# Dosing_CTRLR_HMI.net
KiCad netlist of a schematic drawn in EAGLE
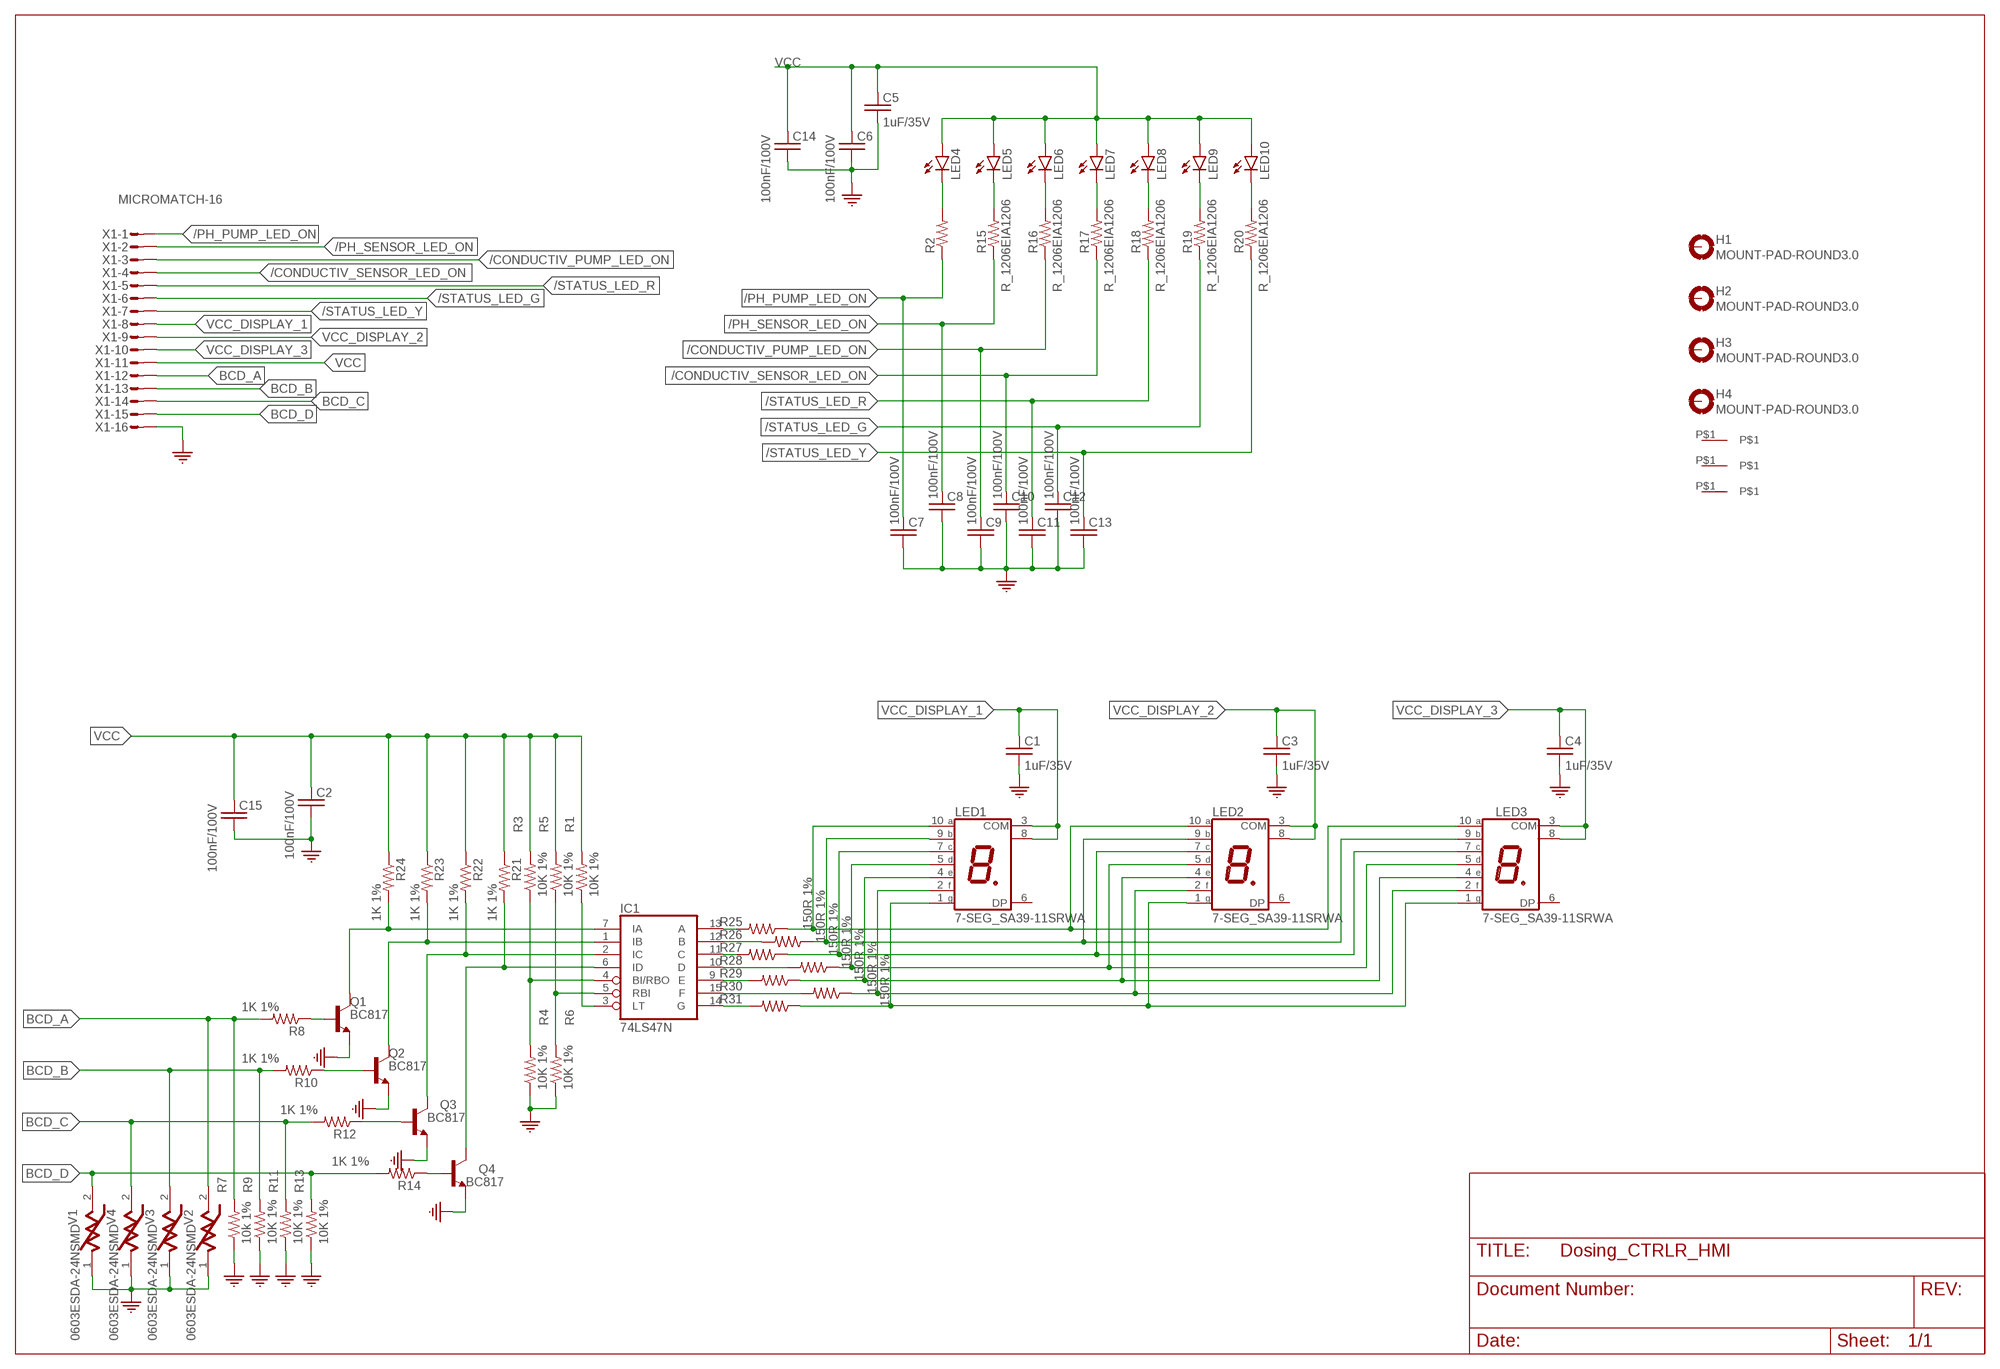
[diagram p0: schematic, sheet 1]

(export (version "E")
  (design (tool "Eeschema 10.0.6"))
  (components
    (comp (ref "C1")
      (value "1uF/35V")
      (footprint "eagle-import:EIA0603")
      (libsource (lib "eagle-import") (part "C_0603EIA0603"))
    )
    (comp (ref "C2")
      (value "100nF/100V")
      (footprint "eagle-import:EIA0603")
      (libsource (lib "eagle-import") (part "C_0603EIA0603"))
    )
    (comp (ref "C3")
      (value "1uF/35V")
      (footprint "eagle-import:EIA0603")
      (libsource (lib "eagle-import") (part "C_0603EIA0603"))
    )
    (comp (ref "C4")
      (value "1uF/35V")
      (footprint "eagle-import:EIA0603")
      (libsource (lib "eagle-import") (part "C_0603EIA0603"))
    )
    (comp (ref "C5")
      (value "1uF/35V")
      (footprint "eagle-import:EIA0603")
      (libsource (lib "eagle-import") (part "C_0603EIA0603"))
    )
    (comp (ref "C6")
      (value "100nF/100V")
      (footprint "eagle-import:EIA0603")
      (libsource (lib "eagle-import") (part "C_0603EIA0603"))
    )
    (comp (ref "C7")
      (value "100nF/100V")
      (footprint "eagle-import:EIA0603")
      (libsource (lib "eagle-import") (part "C_0603EIA0603"))
    )
    (comp (ref "C8")
      (value "100nF/100V")
      (footprint "eagle-import:EIA0603")
      (libsource (lib "eagle-import") (part "C_0603EIA0603"))
    )
    (comp (ref "C9")
      (value "100nF/100V")
      (footprint "eagle-import:EIA0603")
      (libsource (lib "eagle-import") (part "C_0603EIA0603"))
    )
    (comp (ref "C10")
      (value "100nF/100V")
      (footprint "eagle-import:EIA0603")
      (libsource (lib "eagle-import") (part "C_0603EIA0603"))
    )
    (comp (ref "C11")
      (value "100nF/100V")
      (footprint "eagle-import:EIA0603")
      (libsource (lib "eagle-import") (part "C_0603EIA0603"))
    )
    (comp (ref "C12")
      (value "100nF/100V")
      (footprint "eagle-import:EIA0603")
      (libsource (lib "eagle-import") (part "C_0603EIA0603"))
    )
    (comp (ref "C13")
      (value "100nF/100V")
      (footprint "eagle-import:EIA0603")
      (libsource (lib "eagle-import") (part "C_0603EIA0603"))
    )
    (comp (ref "C14")
      (value "100nF/100V")
      (footprint "eagle-import:EIA0603")
      (libsource (lib "eagle-import") (part "C_0603EIA0603"))
    )
    (comp (ref "C15")
      (value "100nF/100V")
      (footprint "eagle-import:EIA0603")
      (libsource (lib "eagle-import") (part "C_0603EIA0603"))
    )
    (comp (ref "FID1")
      (value "FIDUCIAL")
      (footprint "eagle-import:FIDUCIAL")
      (libsource (lib "eagle-import") (part "FIDUCIAL"))
    )
    (comp (ref "FID2")
      (value "FIDUCIAL")
      (footprint "eagle-import:FIDUCIAL")
      (libsource (lib "eagle-import") (part "FIDUCIAL"))
    )
    (comp (ref "FID3")
      (value "FIDUCIAL")
      (footprint "eagle-import:FIDUCIAL")
      (libsource (lib "eagle-import") (part "FIDUCIAL"))
    )
    (comp (ref "H1")
      (value "MOUNT-PAD-ROUND3.0")
      (footprint "eagle-import:3,0-PAD")
      (libsource (lib "eagle-import") (part "MOUNT-PAD-ROUND3.0"))
    )
    (comp (ref "H2")
      (value "MOUNT-PAD-ROUND3.0")
      (footprint "eagle-import:3,0-PAD")
      (libsource (lib "eagle-import") (part "MOUNT-PAD-ROUND3.0"))
    )
    (comp (ref "H3")
      (value "MOUNT-PAD-ROUND3.0")
      (footprint "eagle-import:3,0-PAD")
      (libsource (lib "eagle-import") (part "MOUNT-PAD-ROUND3.0"))
    )
    (comp (ref "H4")
      (value "MOUNT-PAD-ROUND3.0")
      (footprint "eagle-import:3,0-PAD")
      (libsource (lib "eagle-import") (part "MOUNT-PAD-ROUND3.0"))
    )
    (comp (ref "IC1")
      (value "74LS47N")
      (footprint "eagle-import:DIL16")
      (libsource (lib "eagle-import") (part "7447NLS"))
    )
    (comp (ref "LED1")
      (value "7-SEG_SA39-11SRWA")
      (footprint "eagle-import:SA39-11SRWA")
      (libsource (lib "eagle-import") (part "7-SEG_SA39-11SRWA"))
    )
    (comp (ref "LED2")
      (value "7-SEG_SA39-11SRWA")
      (footprint "eagle-import:SA39-11SRWA")
      (libsource (lib "eagle-import") (part "7-SEG_SA39-11SRWA"))
    )
    (comp (ref "LED3")
      (value "7-SEG_SA39-11SRWA")
      (footprint "eagle-import:SA39-11SRWA")
      (libsource (lib "eagle-import") (part "7-SEG_SA39-11SRWA"))
    )
    (comp (ref "LED4")
      (value "LED5MM")
      (footprint "eagle-import:LED5MM")
      (libsource (lib "eagle-import") (part "LED5MM"))
    )
    (comp (ref "LED5")
      (value "LED5MM")
      (footprint "eagle-import:LED5MM")
      (libsource (lib "eagle-import") (part "LED5MM"))
    )
    (comp (ref "LED6")
      (value "LED5MM")
      (footprint "eagle-import:LED5MM")
      (libsource (lib "eagle-import") (part "LED5MM"))
    )
    (comp (ref "LED7")
      (value "LED5MM")
      (footprint "eagle-import:LED5MM")
      (libsource (lib "eagle-import") (part "LED5MM"))
    )
    (comp (ref "LED8")
      (value "LED5MM")
      (footprint "eagle-import:LED5MM")
      (libsource (lib "eagle-import") (part "LED5MM"))
    )
    (comp (ref "LED9")
      (value "LED5MM")
      (footprint "eagle-import:LED5MM")
      (libsource (lib "eagle-import") (part "LED5MM"))
    )
    (comp (ref "LED10")
      (value "LED5MM")
      (footprint "eagle-import:LED5MM")
      (libsource (lib "eagle-import") (part "LED5MM"))
    )
    (comp (ref "Q1")
      (value "BC817")
      (footprint "eagle-import:SOT23")
      (fields (field (name "MFR") "NXP"))
      (libsource (lib "eagle-import") (part "BC817"))
    )
    (comp (ref "Q2")
      (value "BC817")
      (footprint "eagle-import:SOT23")
      (fields (field (name "MFR") "NXP"))
      (libsource (lib "eagle-import") (part "BC817"))
    )
    (comp (ref "Q3")
      (value "BC817")
      (footprint "eagle-import:SOT23")
      (fields (field (name "MFR") "NXP"))
      (libsource (lib "eagle-import") (part "BC817"))
    )
    (comp (ref "Q4")
      (value "BC817")
      (footprint "eagle-import:SOT23")
      (fields (field (name "MFR") "NXP"))
      (libsource (lib "eagle-import") (part "BC817"))
    )
    (comp (ref "R1")
      (value "10K 1%")
      (footprint "eagle-import:EIA0603")
      (libsource (lib "eagle-import") (part "R_0603"))
    )
    (comp (ref "R2")
      (value "R_1206EIA1206")
      (footprint "eagle-import:EIA1206")
      (libsource (lib "eagle-import") (part "R_1206EIA1206"))
    )
    (comp (ref "R3")
      (value "10K 1%")
      (footprint "eagle-import:EIA0603")
      (libsource (lib "eagle-import") (part "R_0603"))
    )
    (comp (ref "R4")
      (value "10K 1%")
      (footprint "eagle-import:EIA0603")
      (libsource (lib "eagle-import") (part "R_0603"))
    )
    (comp (ref "R5")
      (value "10K 1%")
      (footprint "eagle-import:EIA0603")
      (libsource (lib "eagle-import") (part "R_0603"))
    )
    (comp (ref "R6")
      (value "10K 1%")
      (footprint "eagle-import:EIA0603")
      (libsource (lib "eagle-import") (part "R_0603"))
    )
    (comp (ref "R7")
      (value "10k 1%")
      (footprint "eagle-import:EIA0603")
      (libsource (lib "eagle-import") (part "R_0603"))
    )
    (comp (ref "R8")
      (value "1K 1%")
      (footprint "eagle-import:EIA0603")
      (libsource (lib "eagle-import") (part "R_0603"))
    )
    (comp (ref "R9")
      (value "10K 1%")
      (footprint "eagle-import:EIA0603")
      (libsource (lib "eagle-import") (part "R_0603"))
    )
    (comp (ref "R10")
      (value "1K 1%")
      (footprint "eagle-import:EIA0603")
      (libsource (lib "eagle-import") (part "R_0603"))
    )
    (comp (ref "R11")
      (value "10K 1%")
      (footprint "eagle-import:EIA0603")
      (libsource (lib "eagle-import") (part "R_0603"))
    )
    (comp (ref "R12")
      (value "1K 1%")
      (footprint "eagle-import:EIA0603")
      (libsource (lib "eagle-import") (part "R_0603"))
    )
    (comp (ref "R13")
      (value "10K 1%")
      (footprint "eagle-import:EIA0603")
      (libsource (lib "eagle-import") (part "R_0603"))
    )
    (comp (ref "R14")
      (value "1K 1%")
      (footprint "eagle-import:EIA0603")
      (libsource (lib "eagle-import") (part "R_0603"))
    )
    (comp (ref "R15")
      (value "R_1206EIA1206")
      (footprint "eagle-import:EIA1206")
      (libsource (lib "eagle-import") (part "R_1206EIA1206"))
    )
    (comp (ref "R16")
      (value "R_1206EIA1206")
      (footprint "eagle-import:EIA1206")
      (libsource (lib "eagle-import") (part "R_1206EIA1206"))
    )
    (comp (ref "R17")
      (value "R_1206EIA1206")
      (footprint "eagle-import:EIA1206")
      (libsource (lib "eagle-import") (part "R_1206EIA1206"))
    )
    (comp (ref "R18")
      (value "R_1206EIA1206")
      (footprint "eagle-import:EIA1206")
      (libsource (lib "eagle-import") (part "R_1206EIA1206"))
    )
    (comp (ref "R19")
      (value "R_1206EIA1206")
      (footprint "eagle-import:EIA1206")
      (libsource (lib "eagle-import") (part "R_1206EIA1206"))
    )
    (comp (ref "R20")
      (value "R_1206EIA1206")
      (footprint "eagle-import:EIA1206")
      (libsource (lib "eagle-import") (part "R_1206EIA1206"))
    )
    (comp (ref "R21")
      (value "1K 1%")
      (footprint "eagle-import:EIA0603")
      (libsource (lib "eagle-import") (part "R_0603"))
    )
    (comp (ref "R22")
      (value "1K 1%")
      (footprint "eagle-import:EIA0603")
      (libsource (lib "eagle-import") (part "R_0603"))
    )
    (comp (ref "R23")
      (value "1K 1%")
      (footprint "eagle-import:EIA0603")
      (libsource (lib "eagle-import") (part "R_0603"))
    )
    (comp (ref "R24")
      (value "1K 1%")
      (footprint "eagle-import:EIA0603")
      (libsource (lib "eagle-import") (part "R_0603"))
    )
    (comp (ref "R25")
      (value "150R 1%")
      (footprint "eagle-import:EIA1206")
      (libsource (lib "eagle-import") (part "R_1206EIA1206"))
    )
    (comp (ref "R26")
      (value "150R 1%")
      (footprint "eagle-import:EIA1206")
      (libsource (lib "eagle-import") (part "R_1206EIA1206"))
    )
    (comp (ref "R27")
      (value "150R 1%")
      (footprint "eagle-import:EIA1206")
      (libsource (lib "eagle-import") (part "R_1206EIA1206"))
    )
    (comp (ref "R28")
      (value "150R 1%")
      (footprint "eagle-import:EIA1206")
      (libsource (lib "eagle-import") (part "R_1206EIA1206"))
    )
    (comp (ref "R29")
      (value "150R 1%")
      (footprint "eagle-import:EIA1206")
      (libsource (lib "eagle-import") (part "R_1206EIA1206"))
    )
    (comp (ref "R30")
      (value "150R 1%")
      (footprint "eagle-import:EIA1206")
      (libsource (lib "eagle-import") (part "R_1206EIA1206"))
    )
    (comp (ref "R31")
      (value "150R 1%")
      (footprint "eagle-import:EIA1206")
      (libsource (lib "eagle-import") (part "R_1206EIA1206"))
    )
    (comp (ref "V1")
      (value "0603ESDA-24NSMD")
      (footprint "eagle-import:EIA0603")
      (fields (field (name "MFR") "Bourns"))
      (libsource (lib "eagle-import") (part "0603ESDA-24NSMD"))
    )
    (comp (ref "V2")
      (value "0603ESDA-24NSMD")
      (footprint "eagle-import:EIA0603")
      (fields (field (name "MFR") "Bourns"))
      (libsource (lib "eagle-import") (part "0603ESDA-24NSMD"))
    )
    (comp (ref "V3")
      (value "0603ESDA-24NSMD")
      (footprint "eagle-import:EIA0603")
      (fields (field (name "MFR") "Bourns"))
      (libsource (lib "eagle-import") (part "0603ESDA-24NSMD"))
    )
    (comp (ref "V4")
      (value "0603ESDA-24NSMD")
      (footprint "eagle-import:EIA0603")
      (fields (field (name "MFR") "Bourns"))
      (libsource (lib "eagle-import") (part "0603ESDA-24NSMD"))
    )
    (comp (ref "X1")
      (value "MICROMATCH-16")
      (footprint "eagle-import:MICROMATCH-16")
      (fields (field (name "MF") "FARNELL") (field (name "MPN") "8-215464-6"))
      (libsource (lib "eagle-import") (part "MICROMATCH-16"))
    )
  )
  (nets
    (net (code "1") (name "BCD_A") (class "Default")
      (node (ref "R7") (pin "2") (pinfunction "2_2") (pintype "passive"))
      (node (ref "R8") (pin "2") (pinfunction "2_2") (pintype "passive"))
      (node (ref "V2") (pin "2") (pinfunction "2_2") (pintype "passive"))
      (node (ref "X1") (pin "12") (pinfunction "S_12") (pintype "passive"))
    )
    (net (code "2") (name "BCD_B") (class "Default")
      (node (ref "R10") (pin "2") (pinfunction "2_2") (pintype "passive"))
      (node (ref "R9") (pin "2") (pinfunction "2_2") (pintype "passive"))
      (node (ref "V3") (pin "2") (pinfunction "2_2") (pintype "passive"))
      (node (ref "X1") (pin "13") (pinfunction "S_13") (pintype "passive"))
    )
    (net (code "3") (name "BCD_C") (class "Default")
      (node (ref "R11") (pin "2") (pinfunction "2_2") (pintype "passive"))
      (node (ref "R12") (pin "2") (pinfunction "2_2") (pintype "passive"))
      (node (ref "V4") (pin "2") (pinfunction "2_2") (pintype "passive"))
      (node (ref "X1") (pin "14") (pinfunction "S_14") (pintype "passive"))
    )
    (net (code "4") (name "BCD_D") (class "Default")
      (node (ref "R13") (pin "2") (pinfunction "2_2") (pintype "passive"))
      (node (ref "R14") (pin "2") (pinfunction "2_2") (pintype "passive"))
      (node (ref "V1") (pin "2") (pinfunction "2_2") (pintype "passive"))
      (node (ref "X1") (pin "15") (pinfunction "S_15") (pintype "passive"))
    )
    (net (code "5") (name "GND") (class "Default")
      (node (ref "C1") (pin "2") (pinfunction "2_2") (pintype "passive"))
      (node (ref "C10") (pin "2") (pinfunction "2_2") (pintype "passive"))
      (node (ref "C11") (pin "2") (pinfunction "2_2") (pintype "passive"))
      (node (ref "C12") (pin "2") (pinfunction "2_2") (pintype "passive"))
      (node (ref "C13") (pin "2") (pinfunction "2_2") (pintype "passive"))
      (node (ref "C14") (pin "2") (pinfunction "2_2") (pintype "passive"))
      (node (ref "C15") (pin "2") (pinfunction "2_2") (pintype "passive"))
      (node (ref "C2") (pin "2") (pinfunction "2_2") (pintype "passive"))
      (node (ref "C3") (pin "2") (pinfunction "2_2") (pintype "passive"))
      (node (ref "C4") (pin "2") (pinfunction "2_2") (pintype "passive"))
      (node (ref "C5") (pin "2") (pinfunction "2_2") (pintype "passive"))
      (node (ref "C6") (pin "2") (pinfunction "2_2") (pintype "passive"))
      (node (ref "C7") (pin "2") (pinfunction "2_2") (pintype "passive"))
      (node (ref "C8") (pin "2") (pinfunction "2_2") (pintype "passive"))
      (node (ref "C9") (pin "2") (pinfunction "2_2") (pintype "passive"))
      (node (ref "Q1") (pin "2") (pinfunction "E_2") (pintype "passive"))
      (node (ref "Q2") (pin "2") (pinfunction "E_2") (pintype "passive"))
      (node (ref "Q3") (pin "2") (pinfunction "E_2") (pintype "passive"))
      (node (ref "Q4") (pin "2") (pinfunction "E_2") (pintype "passive"))
      (node (ref "R11") (pin "1") (pinfunction "1_1") (pintype "passive"))
      (node (ref "R13") (pin "1") (pinfunction "1_1") (pintype "passive"))
      (node (ref "R4") (pin "1") (pinfunction "1_1") (pintype "passive"))
      (node (ref "R6") (pin "1") (pinfunction "1_1") (pintype "passive"))
      (node (ref "R7") (pin "1") (pinfunction "1_1") (pintype "passive"))
      (node (ref "R9") (pin "1") (pinfunction "1_1") (pintype "passive"))
      (node (ref "V1") (pin "1") (pinfunction "1_1") (pintype "passive"))
      (node (ref "V2") (pin "1") (pinfunction "1_1") (pintype "passive"))
      (node (ref "V3") (pin "1") (pinfunction "1_1") (pintype "passive"))
      (node (ref "V4") (pin "1") (pinfunction "1_1") (pintype "passive"))
      (node (ref "X1") (pin "16") (pinfunction "S_16") (pintype "passive"))
    )
    (net (code "6") (name "Net-(IC1A-A)") (class "Default")
      (node (ref "IC1") (pin "13") (pinfunction "A_13") (pintype "output"))
      (node (ref "R25") (pin "2") (pinfunction "2_2") (pintype "passive"))
    )
    (net (code "7") (name "Net-(IC1A-B)") (class "Default")
      (node (ref "IC1") (pin "12") (pinfunction "B_12") (pintype "output"))
      (node (ref "R26") (pin "2") (pinfunction "2_2") (pintype "passive"))
    )
    (net (code "8") (name "Net-(IC1A-BI{slash}RBO)") (class "Default")
      (node (ref "IC1") (pin "4") (pinfunction "BI/RBO_4") (pintype "input"))
      (node (ref "R3") (pin "1") (pinfunction "1_1") (pintype "passive"))
      (node (ref "R4") (pin "2") (pinfunction "2_2") (pintype "passive"))
    )
    (net (code "9") (name "Net-(IC1A-C)") (class "Default")
      (node (ref "IC1") (pin "11") (pinfunction "C_11") (pintype "output"))
      (node (ref "R27") (pin "2") (pinfunction "2_2") (pintype "passive"))
    )
    (net (code "10") (name "Net-(IC1A-D)") (class "Default")
      (node (ref "IC1") (pin "10") (pinfunction "D_10") (pintype "output"))
      (node (ref "R28") (pin "2") (pinfunction "2_2") (pintype "passive"))
    )
    (net (code "11") (name "Net-(IC1A-E)") (class "Default")
      (node (ref "IC1") (pin "9") (pinfunction "E_9") (pintype "output"))
      (node (ref "R29") (pin "2") (pinfunction "2_2") (pintype "passive"))
    )
    (net (code "12") (name "Net-(IC1A-F)") (class "Default")
      (node (ref "IC1") (pin "15") (pinfunction "F_15") (pintype "output"))
      (node (ref "R30") (pin "2") (pinfunction "2_2") (pintype "passive"))
    )
    (net (code "13") (name "Net-(IC1A-G)") (class "Default")
      (node (ref "IC1") (pin "14") (pinfunction "G_14") (pintype "output"))
      (node (ref "R31") (pin "2") (pinfunction "2_2") (pintype "passive"))
    )
    (net (code "14") (name "Net-(IC1A-IA)") (class "Default")
      (node (ref "IC1") (pin "7") (pinfunction "IA_7") (pintype "input"))
      (node (ref "Q1") (pin "3") (pinfunction "C_3") (pintype "passive"))
      (node (ref "R24") (pin "2") (pinfunction "2_2") (pintype "passive"))
    )
    (net (code "15") (name "Net-(IC1A-IB)") (class "Default")
      (node (ref "IC1") (pin "1") (pinfunction "IB_1") (pintype "input"))
      (node (ref "Q2") (pin "3") (pinfunction "C_3") (pintype "passive"))
      (node (ref "R23") (pin "2") (pinfunction "2_2") (pintype "passive"))
    )
    (net (code "16") (name "Net-(IC1A-IC)") (class "Default")
      (node (ref "IC1") (pin "2") (pinfunction "IC_2") (pintype "input"))
      (node (ref "Q3") (pin "3") (pinfunction "C_3") (pintype "passive"))
      (node (ref "R22") (pin "2") (pinfunction "2_2") (pintype "passive"))
    )
    (net (code "17") (name "Net-(IC1A-ID)") (class "Default")
      (node (ref "IC1") (pin "6") (pinfunction "ID_6") (pintype "input"))
      (node (ref "Q4") (pin "3") (pinfunction "C_3") (pintype "passive"))
      (node (ref "R21") (pin "2") (pinfunction "2_2") (pintype "passive"))
    )
    (net (code "18") (name "Net-(IC1A-LT)") (class "Default")
      (node (ref "IC1") (pin "3") (pinfunction "LT_3") (pintype "input"))
      (node (ref "R1") (pin "1") (pinfunction "1_1") (pintype "passive"))
    )
    (net (code "19") (name "Net-(IC1A-RBI)") (class "Default")
      (node (ref "IC1") (pin "5") (pinfunction "RBI_5") (pintype "input"))
      (node (ref "R5") (pin "1") (pinfunction "1_1") (pintype "passive"))
      (node (ref "R6") (pin "2") (pinfunction "2_2") (pintype "passive"))
    )
    (net (code "20") (name "Net-(LED1-A)") (class "Default")
      (node (ref "LED1") (pin "10") (pinfunction "A_10") (pintype "passive"))
      (node (ref "LED2") (pin "10") (pinfunction "A_10") (pintype "passive"))
      (node (ref "LED3") (pin "10") (pinfunction "A_10") (pintype "passive"))
      (node (ref "R25") (pin "1") (pinfunction "1_1") (pintype "passive"))
    )
    (net (code "21") (name "Net-(LED1-B)") (class "Default")
      (node (ref "LED1") (pin "9") (pinfunction "B_9") (pintype "passive"))
      (node (ref "LED2") (pin "9") (pinfunction "B_9") (pintype "passive"))
      (node (ref "LED3") (pin "9") (pinfunction "B_9") (pintype "passive"))
      (node (ref "R26") (pin "1") (pinfunction "1_1") (pintype "passive"))
    )
    (net (code "22") (name "Net-(LED1-C)") (class "Default")
      (node (ref "LED1") (pin "7") (pinfunction "C_7") (pintype "passive"))
      (node (ref "LED2") (pin "7") (pinfunction "C_7") (pintype "passive"))
      (node (ref "LED3") (pin "7") (pinfunction "C_7") (pintype "passive"))
      (node (ref "R27") (pin "1") (pinfunction "1_1") (pintype "passive"))
    )
    (net (code "23") (name "Net-(LED1-D)") (class "Default")
      (node (ref "LED1") (pin "5") (pinfunction "D_5") (pintype "passive"))
      (node (ref "LED2") (pin "5") (pinfunction "D_5") (pintype "passive"))
      (node (ref "LED3") (pin "5") (pinfunction "D_5") (pintype "passive"))
      (node (ref "R28") (pin "1") (pinfunction "1_1") (pintype "passive"))
    )
    (net (code "24") (name "Net-(LED1-E)") (class "Default")
      (node (ref "LED1") (pin "4") (pinfunction "E_4") (pintype "passive"))
      (node (ref "LED2") (pin "4") (pinfunction "E_4") (pintype "passive"))
      (node (ref "LED3") (pin "4") (pinfunction "E_4") (pintype "passive"))
      (node (ref "R29") (pin "1") (pinfunction "1_1") (pintype "passive"))
    )
    (net (code "25") (name "Net-(LED1-F)") (class "Default")
      (node (ref "LED1") (pin "2") (pinfunction "F_2") (pintype "passive"))
      (node (ref "LED2") (pin "2") (pinfunction "F_2") (pintype "passive"))
      (node (ref "LED3") (pin "2") (pinfunction "F_2") (pintype "passive"))
      (node (ref "R30") (pin "1") (pinfunction "1_1") (pintype "passive"))
    )
    (net (code "26") (name "Net-(LED1-G)") (class "Default")
      (node (ref "LED1") (pin "1") (pinfunction "G_1") (pintype "passive"))
      (node (ref "LED2") (pin "1") (pinfunction "G_1") (pintype "passive"))
      (node (ref "LED3") (pin "1") (pinfunction "G_1") (pintype "passive"))
      (node (ref "R31") (pin "1") (pinfunction "1_1") (pintype "passive"))
    )
    (net (code "27") (name "Net-(LED4-C)") (class "Default")
      (node (ref "LED4") (pin "K") (pinfunction "C_K") (pintype "passive"))
      (node (ref "R2") (pin "2") (pinfunction "2_2") (pintype "passive"))
    )
    (net (code "28") (name "Net-(LED5-C)") (class "Default")
      (node (ref "LED5") (pin "K") (pinfunction "C_K") (pintype "passive"))
      (node (ref "R15") (pin "2") (pinfunction "2_2") (pintype "passive"))
    )
    (net (code "29") (name "Net-(LED6-C)") (class "Default")
      (node (ref "LED6") (pin "K") (pinfunction "C_K") (pintype "passive"))
      (node (ref "R16") (pin "2") (pinfunction "2_2") (pintype "passive"))
    )
    (net (code "30") (name "Net-(LED7-C)") (class "Default")
      (node (ref "LED7") (pin "K") (pinfunction "C_K") (pintype "passive"))
      (node (ref "R17") (pin "2") (pinfunction "2_2") (pintype "passive"))
    )
    (net (code "31") (name "Net-(LED8-C)") (class "Default")
      (node (ref "LED8") (pin "K") (pinfunction "C_K") (pintype "passive"))
      (node (ref "R18") (pin "2") (pinfunction "2_2") (pintype "passive"))
    )
    (net (code "32") (name "Net-(LED9-C)") (class "Default")
      (node (ref "LED9") (pin "K") (pinfunction "C_K") (pintype "passive"))
      (node (ref "R19") (pin "2") (pinfunction "2_2") (pintype "passive"))
    )
    (net (code "33") (name "Net-(LED10-C)") (class "Default")
      (node (ref "LED10") (pin "K") (pinfunction "C_K") (pintype "passive"))
      (node (ref "R20") (pin "2") (pinfunction "2_2") (pintype "passive"))
    )
    (net (code "34") (name "Net-(Q1-B)") (class "Default")
      (node (ref "Q1") (pin "1") (pinfunction "B_1") (pintype "passive"))
      (node (ref "R8") (pin "1") (pinfunction "1_1") (pintype "passive"))
    )
    (net (code "35") (name "Net-(Q2-B)") (class "Default")
      (node (ref "Q2") (pin "1") (pinfunction "B_1") (pintype "passive"))
      (node (ref "R10") (pin "1") (pinfunction "1_1") (pintype "passive"))
    )
    (net (code "36") (name "Net-(Q3-B)") (class "Default")
      (node (ref "Q3") (pin "1") (pinfunction "B_1") (pintype "passive"))
      (node (ref "R12") (pin "1") (pinfunction "1_1") (pintype "passive"))
    )
    (net (code "37") (name "Net-(Q4-B)") (class "Default")
      (node (ref "Q4") (pin "1") (pinfunction "B_1") (pintype "passive"))
      (node (ref "R14") (pin "1") (pinfunction "1_1") (pintype "passive"))
    )
    (net (code "38") (name "VCC") (class "Default")
      (node (ref "C14") (pin "1") (pinfunction "1_1") (pintype "passive"))
      (node (ref "C15") (pin "1") (pinfunction "1_1") (pintype "passive"))
      (node (ref "C2") (pin "1") (pinfunction "1_1") (pintype "passive"))
      (node (ref "C5") (pin "1") (pinfunction "1_1") (pintype "passive"))
      (node (ref "C6") (pin "1") (pinfunction "1_1") (pintype "passive"))
      (node (ref "LED10") (pin "A") (pinfunction "A_A") (pintype "passive"))
      (node (ref "LED4") (pin "A") (pinfunction "A_A") (pintype "passive"))
      (node (ref "LED5") (pin "A") (pinfunction "A_A") (pintype "passive"))
      (node (ref "LED6") (pin "A") (pinfunction "A_A") (pintype "passive"))
      (node (ref "LED7") (pin "A") (pinfunction "A_A") (pintype "passive"))
      (node (ref "LED8") (pin "A") (pinfunction "A_A") (pintype "passive"))
      (node (ref "LED9") (pin "A") (pinfunction "A_A") (pintype "passive"))
      (node (ref "R1") (pin "2") (pinfunction "2_2") (pintype "passive"))
      (node (ref "R21") (pin "1") (pinfunction "1_1") (pintype "passive"))
      (node (ref "R22") (pin "1") (pinfunction "1_1") (pintype "passive"))
      (node (ref "R23") (pin "1") (pinfunction "1_1") (pintype "passive"))
      (node (ref "R24") (pin "1") (pinfunction "1_1") (pintype "passive"))
      (node (ref "R3") (pin "2") (pinfunction "2_2") (pintype "passive"))
      (node (ref "R5") (pin "2") (pinfunction "2_2") (pintype "passive"))
      (node (ref "X1") (pin "11") (pinfunction "S_11") (pintype "passive"))
    )
    (net (code "39") (name "VCC_DISPLAY_1") (class "Default")
      (node (ref "C1") (pin "1") (pinfunction "1_1") (pintype "passive"))
      (node (ref "LED1") (pin "3") (pinfunction "COM_3") (pintype "passive"))
      (node (ref "LED1") (pin "8") (pinfunction "COM_8") (pintype "passive"))
      (node (ref "X1") (pin "8") (pinfunction "S_8") (pintype "passive"))
    )
    (net (code "40") (name "VCC_DISPLAY_2") (class "Default")
      (node (ref "C3") (pin "1") (pinfunction "1_1") (pintype "passive"))
      (node (ref "LED2") (pin "3") (pinfunction "COM_3") (pintype "passive"))
      (node (ref "LED2") (pin "8") (pinfunction "COM_8") (pintype "passive"))
      (node (ref "X1") (pin "9") (pinfunction "S_9") (pintype "passive"))
    )
    (net (code "41") (name "VCC_DISPLAY_3") (class "Default")
      (node (ref "C4") (pin "1") (pinfunction "1_1") (pintype "passive"))
      (node (ref "LED3") (pin "3") (pinfunction "COM_3") (pintype "passive"))
      (node (ref "LED3") (pin "8") (pinfunction "COM_8") (pintype "passive"))
      (node (ref "X1") (pin "10") (pinfunction "S_10") (pintype "passive"))
    )
    (net (code "42") (name "unconnected-(FID1-PadP$1)") (class "Default")
      (node (ref "FID1") (pin "P$1") (pinfunction "P$1_P$1") (pintype "bidirectional"))
    )
    (net (code "43") (name "unconnected-(FID2-PadP$1)") (class "Default")
      (node (ref "FID2") (pin "P$1") (pinfunction "P$1_P$1") (pintype "bidirectional"))
    )
    (net (code "44") (name "unconnected-(FID3-PadP$1)") (class "Default")
      (node (ref "FID3") (pin "P$1") (pinfunction "P$1_P$1") (pintype "bidirectional"))
    )
    (net (code "45") (name "unconnected-(H1-MOUNT-PadB3,0)") (class "Default")
      (node (ref "H1") (pin "B3,0") (pinfunction "MOUNT_B3,0") (pintype "passive"))
    )
    (net (code "46") (name "unconnected-(H2-MOUNT-PadB3,0)") (class "Default")
      (node (ref "H2") (pin "B3,0") (pinfunction "MOUNT_B3,0") (pintype "passive"))
    )
    (net (code "47") (name "unconnected-(H3-MOUNT-PadB3,0)") (class "Default")
      (node (ref "H3") (pin "B3,0") (pinfunction "MOUNT_B3,0") (pintype "passive"))
    )
    (net (code "48") (name "unconnected-(H4-MOUNT-PadB3,0)") (class "Default")
      (node (ref "H4") (pin "B3,0") (pinfunction "MOUNT_B3,0") (pintype "passive"))
    )
    (net (code "49") (name "unconnected-(LED1-DP-Pad6)") (class "Default")
      (node (ref "LED1") (pin "6") (pinfunction "DP_6") (pintype "passive"))
    )
    (net (code "50") (name "unconnected-(LED2-DP-Pad6)") (class "Default")
      (node (ref "LED2") (pin "6") (pinfunction "DP_6") (pintype "passive"))
    )
    (net (code "51") (name "unconnected-(LED3-DP-Pad6)") (class "Default")
      (node (ref "LED3") (pin "6") (pinfunction "DP_6") (pintype "passive"))
    )
    (net (code "52") (name "{slash}CONDUCTIV_PUMP_LED_ON") (class "Default")
      (node (ref "C9") (pin "1") (pinfunction "1_1") (pintype "passive"))
      (node (ref "R16") (pin "1") (pinfunction "1_1") (pintype "passive"))
      (node (ref "X1") (pin "3") (pinfunction "S_3") (pintype "passive"))
    )
    (net (code "53") (name "{slash}CONDUCTIV_SENSOR_LED_ON") (class "Default")
      (node (ref "C10") (pin "1") (pinfunction "1_1") (pintype "passive"))
      (node (ref "R17") (pin "1") (pinfunction "1_1") (pintype "passive"))
      (node (ref "X1") (pin "4") (pinfunction "S_4") (pintype "passive"))
    )
    (net (code "54") (name "{slash}PH_PUMP_LED_ON") (class "Default")
      (node (ref "C7") (pin "1") (pinfunction "1_1") (pintype "passive"))
      (node (ref "R2") (pin "1") (pinfunction "1_1") (pintype "passive"))
      (node (ref "X1") (pin "1") (pinfunction "S_1") (pintype "passive"))
    )
    (net (code "55") (name "{slash}PH_SENSOR_LED_ON") (class "Default")
      (node (ref "C8") (pin "1") (pinfunction "1_1") (pintype "passive"))
      (node (ref "R15") (pin "1") (pinfunction "1_1") (pintype "passive"))
      (node (ref "X1") (pin "2") (pinfunction "S_2") (pintype "passive"))
    )
    (net (code "56") (name "{slash}STATUS_LED_G") (class "Default")
      (node (ref "C12") (pin "1") (pinfunction "1_1") (pintype "passive"))
      (node (ref "R19") (pin "1") (pinfunction "1_1") (pintype "passive"))
      (node (ref "X1") (pin "6") (pinfunction "S_6") (pintype "passive"))
    )
    (net (code "57") (name "{slash}STATUS_LED_R") (class "Default")
      (node (ref "C11") (pin "1") (pinfunction "1_1") (pintype "passive"))
      (node (ref "R18") (pin "1") (pinfunction "1_1") (pintype "passive"))
      (node (ref "X1") (pin "5") (pinfunction "S_5") (pintype "passive"))
    )
    (net (code "58") (name "{slash}STATUS_LED_Y") (class "Default")
      (node (ref "C13") (pin "1") (pinfunction "1_1") (pintype "passive"))
      (node (ref "R20") (pin "1") (pinfunction "1_1") (pintype "passive"))
      (node (ref "X1") (pin "7") (pinfunction "S_7") (pintype "passive"))
    )
  )
)
